# 06_Input_Output.net
KiCad netlist of a schematic drawn in Altium Designer
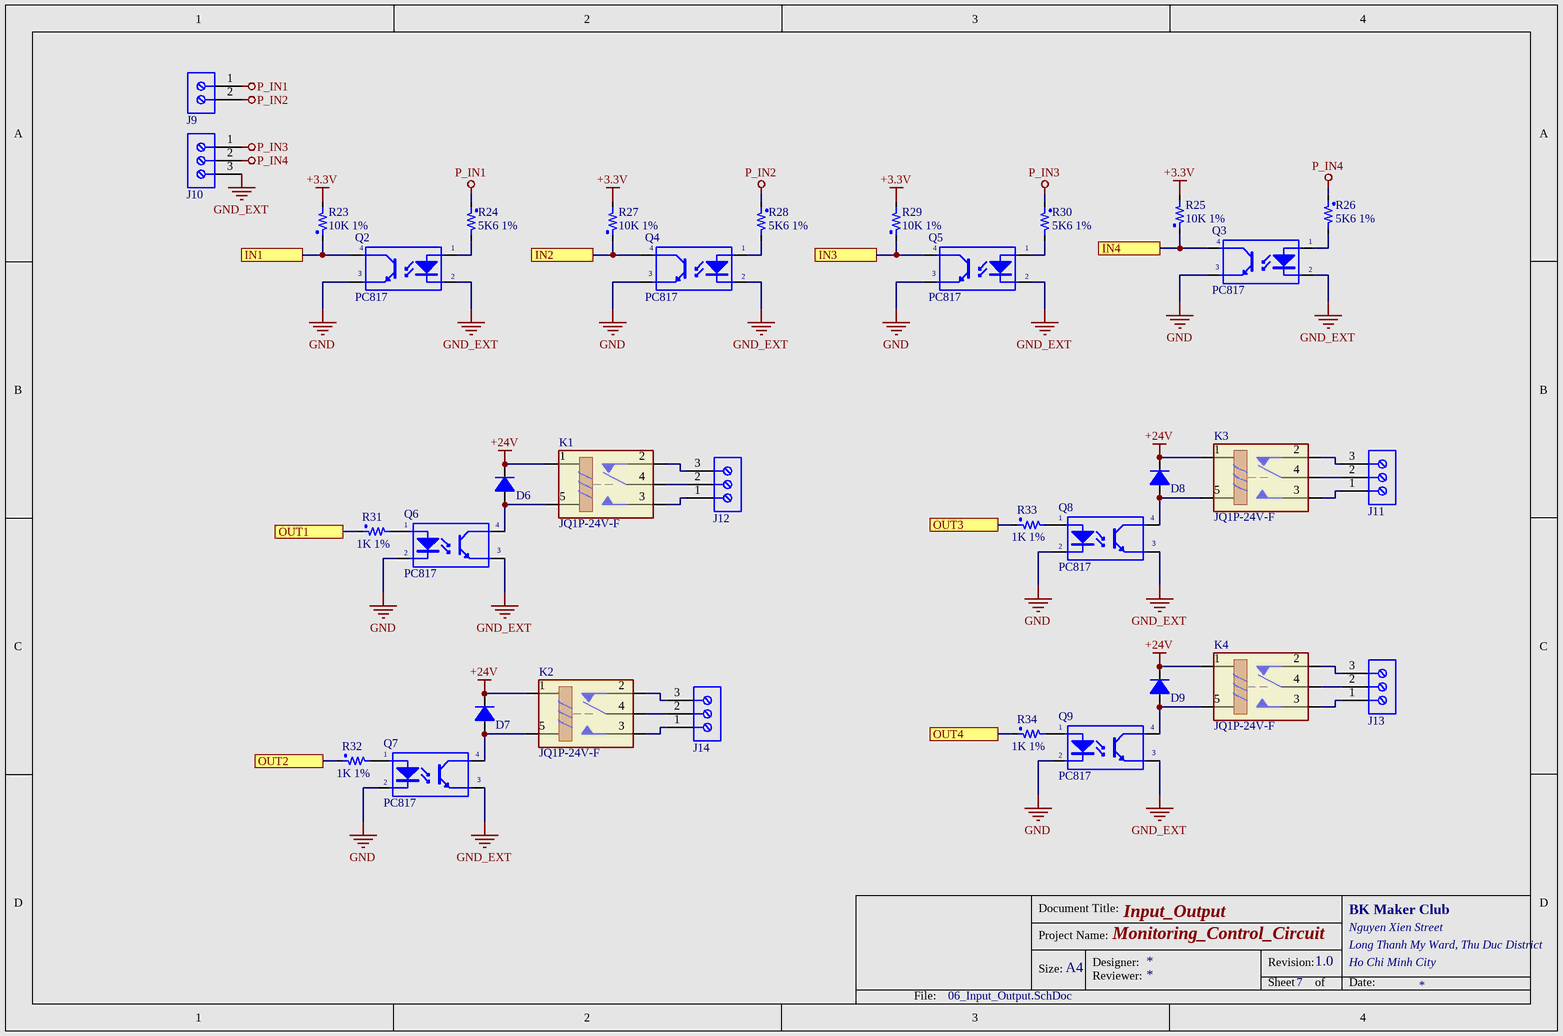
[diagram p0: 06_Input_Output.SchDoc]

(export (version "E")
  (design (tool "Eeschema 10.0.6"))
  (components
    (comp (ref "D6")
      (value "S1M")
      (footprint "Diode:DO-214AC")
      (description "Rectifiers 1.0A 1000V")
      (fields (field (name "MFR") "ON Semiconductor / Fairchild"))
      (libsource (lib "Diode") (part "S1M"))
    )
    (comp (ref "D7")
      (value "S1M")
      (footprint "Diode:DO-214AC")
      (description "Rectifiers 1.0A 1000V")
      (fields (field (name "MFR") "ON Semiconductor / Fairchild"))
      (libsource (lib "Diode") (part "S1M"))
    )
    (comp (ref "D8")
      (value "S1M")
      (footprint "Diode:DO-214AC")
      (description "Rectifiers 1.0A 1000V")
      (fields (field (name "MFR") "ON Semiconductor / Fairchild"))
      (libsource (lib "Diode") (part "S1M"))
    )
    (comp (ref "D9")
      (value "S1M")
      (footprint "Diode:DO-214AC")
      (description "Rectifiers 1.0A 1000V")
      (fields (field (name "MFR") "ON Semiconductor / Fairchild"))
      (libsource (lib "Diode") (part "S1M"))
    )
    (comp (ref "J9")
      (value "691103110002")
      (footprint "691103110002")
      (description "WR-TBL Series 1031 Horizontal Entry Modular, THT, pitch 3.5mm, 2p")
      (fields (field (name "MFR") "Wurth Elektronik"))
      (libsource (lib "Altium_WR-TBL (rev22b)") (part "691103110002"))
    )
    (comp (ref "J10")
      (value "691103110003")
      (footprint "691103110003")
      (description "WR-TBL Series 1031 Horizontal Entry Modular, THT, pitch 3.5mm, 3p")
      (fields (field (name "MFR") "Wurth Elektronik"))
      (libsource (lib "Altium_WR-TBL (rev22b)") (part "691103110003"))
    )
    (comp (ref "J11")
      (value "691103110003")
      (footprint "691103110003")
      (description "WR-TBL Series 1031 Horizontal Entry Modular, THT, pitch 3.5mm, 3p")
      (fields (field (name "MFR") "Wurth Elektronik"))
      (libsource (lib "Altium_WR-TBL (rev22b)") (part "691103110003"))
    )
    (comp (ref "J12")
      (value "691103110003")
      (footprint "691103110003")
      (description "WR-TBL Series 1031 Horizontal Entry Modular, THT, pitch 3.5mm, 3p")
      (fields (field (name "MFR") "Wurth Elektronik"))
      (libsource (lib "Altium_WR-TBL (rev22b)") (part "691103110003"))
    )
    (comp (ref "J13")
      (value "691103110003")
      (footprint "691103110003")
      (description "WR-TBL Series 1031 Horizontal Entry Modular, THT, pitch 3.5mm, 3p")
      (fields (field (name "MFR") "Wurth Elektronik"))
      (libsource (lib "Altium_WR-TBL (rev22b)") (part "691103110003"))
    )
    (comp (ref "J14")
      (value "691103110003")
      (footprint "691103110003")
      (description "WR-TBL Series 1031 Horizontal Entry Modular, THT, pitch 3.5mm, 3p")
      (fields (field (name "MFR") "Wurth Elektronik"))
      (libsource (lib "Altium_WR-TBL (rev22b)") (part "691103110003"))
    )
    (comp (ref "K1")
      (value "JQ1P-24V-F")
      (footprint "JQ1P24VF")
      (description "Relay or Contactor")
      (fields (field (name "MFR") "Panasonic"))
      (libsource (lib "Controller") (part "JQ1P-24V-F"))
    )
    (comp (ref "K2")
      (value "JQ1P-24V-F")
      (footprint "JQ1P24VF")
      (description "Relay or Contactor")
      (fields (field (name "MFR") "Panasonic"))
      (libsource (lib "Controller") (part "JQ1P-24V-F"))
    )
    (comp (ref "K3")
      (value "JQ1P-24V-F")
      (footprint "JQ1P24VF")
      (description "Relay or Contactor")
      (fields (field (name "MFR") "Panasonic"))
      (libsource (lib "Controller") (part "JQ1P-24V-F"))
    )
    (comp (ref "K4")
      (value "JQ1P-24V-F")
      (footprint "JQ1P24VF")
      (description "Relay or Contactor")
      (fields (field (name "MFR") "Panasonic"))
      (libsource (lib "Controller") (part "JQ1P-24V-F"))
    )
    (comp (ref "Q2")
      (value "PC817")
      (footprint "SOP-4")
      (description "Transistor Output Optocouplers Photocoupler")
      (fields (field (name "MFR") "Sharp Microelectronics") (field (name "MFR PART NUMBER") "PC817XNNIP1B"))
      (libsource (lib "Optocoupler") (part "PC817XNNIP1B"))
    )
    (comp (ref "Q3")
      (value "PC817")
      (footprint "SOP-4")
      (description "Transistor Output Optocouplers Photocoupler")
      (fields (field (name "MFR") "Sharp Microelectronics") (field (name "MFR PART NUMBER") "PC817XNNIP1B"))
      (libsource (lib "Optocoupler") (part "PC817XNNIP1B"))
    )
    (comp (ref "Q4")
      (value "PC817")
      (footprint "SOP-4")
      (description "Transistor Output Optocouplers Photocoupler")
      (fields (field (name "MFR") "Sharp Microelectronics") (field (name "MFR PART NUMBER") "PC817XNNIP1B"))
      (libsource (lib "Optocoupler") (part "PC817XNNIP1B"))
    )
    (comp (ref "Q5")
      (value "PC817")
      (footprint "SOP-4")
      (description "Transistor Output Optocouplers Photocoupler")
      (fields (field (name "MFR") "Sharp Microelectronics") (field (name "MFR PART NUMBER") "PC817XNNIP1B"))
      (libsource (lib "Optocoupler") (part "PC817XNNIP1B"))
    )
    (comp (ref "Q6")
      (value "PC817")
      (footprint "SOP-4")
      (description "Transistor Output Optocouplers Photocoupler")
      (fields (field (name "MFR") "Sharp Microelectronics") (field (name "MFR PART NUMBER") "PC817XNNIP1B"))
      (libsource (lib "Optocoupler") (part "PC817XNNIP1B"))
    )
    (comp (ref "Q7")
      (value "PC817")
      (footprint "SOP-4")
      (description "Transistor Output Optocouplers Photocoupler")
      (fields (field (name "MFR") "Sharp Microelectronics") (field (name "MFR PART NUMBER") "PC817XNNIP1B"))
      (libsource (lib "Optocoupler") (part "PC817XNNIP1B"))
    )
    (comp (ref "Q8")
      (value "PC817")
      (footprint "SOP-4")
      (description "Transistor Output Optocouplers Photocoupler")
      (fields (field (name "MFR") "Sharp Microelectronics") (field (name "MFR PART NUMBER") "PC817XNNIP1B"))
      (libsource (lib "Optocoupler") (part "PC817XNNIP1B"))
    )
    (comp (ref "Q9")
      (value "PC817")
      (footprint "SOP-4")
      (description "Transistor Output Optocouplers Photocoupler")
      (fields (field (name "MFR") "Sharp Microelectronics") (field (name "MFR PART NUMBER") "PC817XNNIP1B"))
      (libsource (lib "Optocoupler") (part "PC817XNNIP1B"))
    )
    (comp (ref "R23")
      (value "10K 1%")
      (footprint "Resistor:R0603 (1608 Metric)")
      (description "Thick Film Resistors - SMD 10K OHM 1% Case 0603")
      (fields (field (name "MFR PART NUMBER") "RC0603FR-0710KL") (field (name "MFR") "Yageo"))
      (libsource (lib "ChipResistor") (part "RC0603FR-0710KL"))
    )
    (comp (ref "R24")
      (value "5K6 1%")
      (footprint "Resistor:R0603 (1608 Metric)")
      (description "Thick Film Resistors - SMD 5K6 OHM 1% Case 0603")
      (fields (field (name "MFR PART NUMBER") "RC0603FR-075K6L") (field (name "MFR") "Yageo"))
      (libsource (lib "ChipResistor") (part "RC0603FR-075K6L"))
    )
    (comp (ref "R25")
      (value "10K 1%")
      (footprint "Resistor:R0603 (1608 Metric)")
      (description "Thick Film Resistors - SMD 10K OHM 1% Case 0603")
      (fields (field (name "MFR PART NUMBER") "RC0603FR-0710KL") (field (name "MFR") "Yageo"))
      (libsource (lib "ChipResistor") (part "RC0603FR-0710KL"))
    )
    (comp (ref "R26")
      (value "5K6 1%")
      (footprint "Resistor:R0603 (1608 Metric)")
      (description "Thick Film Resistors - SMD 5K6 OHM 1% Case 0603")
      (fields (field (name "MFR PART NUMBER") "RC0603FR-075K6L") (field (name "MFR") "Yageo"))
      (libsource (lib "ChipResistor") (part "RC0603FR-075K6L"))
    )
    (comp (ref "R27")
      (value "10K 1%")
      (footprint "Resistor:R0603 (1608 Metric)")
      (description "Thick Film Resistors - SMD 10K OHM 1% Case 0603")
      (fields (field (name "MFR PART NUMBER") "RC0603FR-0710KL") (field (name "MFR") "Yageo"))
      (libsource (lib "ChipResistor") (part "RC0603FR-0710KL"))
    )
    (comp (ref "R28")
      (value "5K6 1%")
      (footprint "Resistor:R0603 (1608 Metric)")
      (description "Thick Film Resistors - SMD 5K6 OHM 1% Case 0603")
      (fields (field (name "MFR PART NUMBER") "RC0603FR-075K6L") (field (name "MFR") "Yageo"))
      (libsource (lib "ChipResistor") (part "RC0603FR-075K6L"))
    )
    (comp (ref "R29")
      (value "10K 1%")
      (footprint "Resistor:R0603 (1608 Metric)")
      (description "Thick Film Resistors - SMD 10K OHM 1% Case 0603")
      (fields (field (name "MFR PART NUMBER") "RC0603FR-0710KL") (field (name "MFR") "Yageo"))
      (libsource (lib "ChipResistor") (part "RC0603FR-0710KL"))
    )
    (comp (ref "R30")
      (value "5K6 1%")
      (footprint "Resistor:R0603 (1608 Metric)")
      (description "Thick Film Resistors - SMD 5K6 OHM 1% Case 0603")
      (fields (field (name "MFR PART NUMBER") "RC0603FR-075K6L") (field (name "MFR") "Yageo"))
      (libsource (lib "ChipResistor") (part "RC0603FR-075K6L"))
    )
    (comp (ref "R31")
      (value "1K 1%")
      (footprint "Resistor:R0603 (1608 Metric)")
      (description "Thick Film Resistors - SMD 1K OHM 1% Case 0603")
      (fields (field (name "MFR PART NUMBER") "RC0603FR-071KL") (field (name "MFR") "Yageo"))
      (libsource (lib "ChipResistor") (part "RC0603FR-071KL"))
    )
    (comp (ref "R32")
      (value "1K 1%")
      (footprint "Resistor:R0603 (1608 Metric)")
      (description "Thick Film Resistors - SMD 1K OHM 1% Case 0603")
      (fields (field (name "MFR PART NUMBER") "RC0603FR-071KL") (field (name "MFR") "Yageo"))
      (libsource (lib "ChipResistor") (part "RC0603FR-071KL"))
    )
    (comp (ref "R33")
      (value "1K 1%")
      (footprint "Resistor:R0603 (1608 Metric)")
      (description "Thick Film Resistors - SMD 1K OHM 1% Case 0603")
      (fields (field (name "MFR PART NUMBER") "RC0603FR-071KL") (field (name "MFR") "Yageo"))
      (libsource (lib "ChipResistor") (part "RC0603FR-071KL"))
    )
    (comp (ref "R34")
      (value "1K 1%")
      (footprint "Resistor:R0603 (1608 Metric)")
      (description "Thick Film Resistors - SMD 1K OHM 1% Case 0603")
      (fields (field (name "MFR PART NUMBER") "RC0603FR-071KL") (field (name "MFR") "Yageo"))
      (libsource (lib "ChipResistor") (part "RC0603FR-071KL"))
    )
  )
  (nets
    (net (code "1") (name "+3.3V") (class "Default")
      (node (ref "R23") (pin "2") (pinfunction "2_2") (pintype "passive"))
      (node (ref "R25") (pin "2") (pinfunction "2_2") (pintype "passive"))
      (node (ref "R27") (pin "2") (pinfunction "2_2") (pintype "passive"))
      (node (ref "R29") (pin "2") (pinfunction "2_2") (pintype "passive"))
    )
    (net (code "2") (name "+24V") (class "Default")
      (node (ref "D6") (pin "2") (pinfunction "K_2") (pintype "passive"))
      (node (ref "D7") (pin "2") (pinfunction "K_2") (pintype "passive"))
      (node (ref "D8") (pin "2") (pinfunction "K_2") (pintype "passive"))
      (node (ref "D9") (pin "2") (pinfunction "K_2") (pintype "passive"))
      (node (ref "K1") (pin "1") (pinfunction "COIL1_1") (pintype "passive"))
      (node (ref "K2") (pin "1") (pinfunction "COIL1_1") (pintype "passive"))
      (node (ref "K3") (pin "1") (pinfunction "COIL1_1") (pintype "passive"))
      (node (ref "K4") (pin "1") (pinfunction "COIL1_1") (pintype "passive"))
    )
    (net (code "3") (name "/IN1") (class "Default")
      (node (ref "Q2") (pin "4") (pinfunction "C_4") (pintype "passive"))
      (node (ref "R23") (pin "1") (pinfunction "1_1") (pintype "passive"))
    )
    (net (code "4") (name "/IN2") (class "Default")
      (node (ref "Q4") (pin "4") (pinfunction "C_4") (pintype "passive"))
      (node (ref "R27") (pin "1") (pinfunction "1_1") (pintype "passive"))
    )
    (net (code "5") (name "/IN3") (class "Default")
      (node (ref "Q5") (pin "4") (pinfunction "C_4") (pintype "passive"))
      (node (ref "R29") (pin "1") (pinfunction "1_1") (pintype "passive"))
    )
    (net (code "6") (name "/IN4") (class "Default")
      (node (ref "Q3") (pin "4") (pinfunction "C_4") (pintype "passive"))
      (node (ref "R25") (pin "1") (pinfunction "1_1") (pintype "passive"))
    )
    (net (code "7") (name "/OUT1") (class "Default")
      (node (ref "R31") (pin "1") (pinfunction "1_1") (pintype "passive"))
    )
    (net (code "8") (name "/OUT2") (class "Default")
      (node (ref "R32") (pin "1") (pinfunction "1_1") (pintype "passive"))
    )
    (net (code "9") (name "/OUT3") (class "Default")
      (node (ref "R33") (pin "1") (pinfunction "1_1") (pintype "passive"))
    )
    (net (code "10") (name "/OUT4") (class "Default")
      (node (ref "R34") (pin "1") (pinfunction "1_1") (pintype "passive"))
    )
    (net (code "11") (name "GND") (class "Default")
      (node (ref "Q2") (pin "3") (pinfunction "E_3") (pintype "passive"))
      (node (ref "Q3") (pin "3") (pinfunction "E_3") (pintype "passive"))
      (node (ref "Q4") (pin "3") (pinfunction "E_3") (pintype "passive"))
      (node (ref "Q5") (pin "3") (pinfunction "E_3") (pintype "passive"))
      (node (ref "Q6") (pin "2") (pinfunction "K_2") (pintype "passive"))
      (node (ref "Q7") (pin "2") (pinfunction "K_2") (pintype "passive"))
      (node (ref "Q8") (pin "2") (pinfunction "K_2") (pintype "passive"))
      (node (ref "Q9") (pin "2") (pinfunction "K_2") (pintype "passive"))
    )
    (net (code "12") (name "GND_EXT") (class "Default")
      (node (ref "J10") (pin "3") (pinfunction "3_3") (pintype "passive"))
      (node (ref "Q2") (pin "2") (pinfunction "K_2") (pintype "passive"))
      (node (ref "Q3") (pin "2") (pinfunction "K_2") (pintype "passive"))
      (node (ref "Q4") (pin "2") (pinfunction "K_2") (pintype "passive"))
      (node (ref "Q5") (pin "2") (pinfunction "K_2") (pintype "passive"))
      (node (ref "Q6") (pin "3") (pinfunction "E_3") (pintype "passive"))
      (node (ref "Q7") (pin "3") (pinfunction "E_3") (pintype "passive"))
      (node (ref "Q8") (pin "3") (pinfunction "E_3") (pintype "passive"))
      (node (ref "Q9") (pin "3") (pinfunction "E_3") (pintype "passive"))
    )
    (net (code "13") (name "Net-(D6-A)") (class "Default")
      (node (ref "D6") (pin "1") (pinfunction "A_1") (pintype "passive"))
      (node (ref "K1") (pin "5") (pinfunction "COIL2_5") (pintype "passive"))
      (node (ref "Q6") (pin "4") (pinfunction "C_4") (pintype "passive"))
    )
    (net (code "14") (name "Net-(D7-A)") (class "Default")
      (node (ref "D7") (pin "1") (pinfunction "A_1") (pintype "passive"))
      (node (ref "K2") (pin "5") (pinfunction "COIL2_5") (pintype "passive"))
      (node (ref "Q7") (pin "4") (pinfunction "C_4") (pintype "passive"))
    )
    (net (code "15") (name "Net-(D8-A)") (class "Default")
      (node (ref "D8") (pin "1") (pinfunction "A_1") (pintype "passive"))
      (node (ref "K3") (pin "5") (pinfunction "COIL2_5") (pintype "passive"))
      (node (ref "Q8") (pin "4") (pinfunction "C_4") (pintype "passive"))
    )
    (net (code "16") (name "Net-(D9-A)") (class "Default")
      (node (ref "D9") (pin "1") (pinfunction "A_1") (pintype "passive"))
      (node (ref "K4") (pin "5") (pinfunction "COIL2_5") (pintype "passive"))
      (node (ref "Q9") (pin "4") (pinfunction "C_4") (pintype "passive"))
    )
    (net (code "17") (name "Net-(K1-COM)") (class "Default")
      (node (ref "J12") (pin "2") (pinfunction "2_2") (pintype "passive"))
      (node (ref "K1") (pin "4") (pinfunction "COM_4") (pintype "passive"))
    )
    (net (code "18") (name "Net-(K1-NC)") (class "Default")
      (node (ref "J12") (pin "3") (pinfunction "3_3") (pintype "passive"))
      (node (ref "K1") (pin "2") (pinfunction "NC_2") (pintype "passive"))
    )
    (net (code "19") (name "Net-(K1-NO)") (class "Default")
      (node (ref "J12") (pin "1") (pinfunction "1_1") (pintype "passive"))
      (node (ref "K1") (pin "3") (pinfunction "NO_3") (pintype "passive"))
    )
    (net (code "20") (name "Net-(K2-COM)") (class "Default")
      (node (ref "J14") (pin "2") (pinfunction "2_2") (pintype "passive"))
      (node (ref "K2") (pin "4") (pinfunction "COM_4") (pintype "passive"))
    )
    (net (code "21") (name "Net-(K2-NC)") (class "Default")
      (node (ref "J14") (pin "3") (pinfunction "3_3") (pintype "passive"))
      (node (ref "K2") (pin "2") (pinfunction "NC_2") (pintype "passive"))
    )
    (net (code "22") (name "Net-(K2-NO)") (class "Default")
      (node (ref "J14") (pin "1") (pinfunction "1_1") (pintype "passive"))
      (node (ref "K2") (pin "3") (pinfunction "NO_3") (pintype "passive"))
    )
    (net (code "23") (name "Net-(K3-COM)") (class "Default")
      (node (ref "J11") (pin "2") (pinfunction "2_2") (pintype "passive"))
      (node (ref "K3") (pin "4") (pinfunction "COM_4") (pintype "passive"))
    )
    (net (code "24") (name "Net-(K3-NC)") (class "Default")
      (node (ref "J11") (pin "3") (pinfunction "3_3") (pintype "passive"))
      (node (ref "K3") (pin "2") (pinfunction "NC_2") (pintype "passive"))
    )
    (net (code "25") (name "Net-(K3-NO)") (class "Default")
      (node (ref "J11") (pin "1") (pinfunction "1_1") (pintype "passive"))
      (node (ref "K3") (pin "3") (pinfunction "NO_3") (pintype "passive"))
    )
    (net (code "26") (name "Net-(K4-COM)") (class "Default")
      (node (ref "J13") (pin "2") (pinfunction "2_2") (pintype "passive"))
      (node (ref "K4") (pin "4") (pinfunction "COM_4") (pintype "passive"))
    )
    (net (code "27") (name "Net-(K4-NC)") (class "Default")
      (node (ref "J13") (pin "3") (pinfunction "3_3") (pintype "passive"))
      (node (ref "K4") (pin "2") (pinfunction "NC_2") (pintype "passive"))
    )
    (net (code "28") (name "Net-(K4-NO)") (class "Default")
      (node (ref "J13") (pin "1") (pinfunction "1_1") (pintype "passive"))
      (node (ref "K4") (pin "3") (pinfunction "NO_3") (pintype "passive"))
    )
    (net (code "29") (name "Net-(Q2-A)") (class "Default")
      (node (ref "Q2") (pin "1") (pinfunction "A_1") (pintype "passive"))
      (node (ref "R24") (pin "2") (pinfunction "2_2") (pintype "passive"))
    )
    (net (code "30") (name "Net-(Q3-A)") (class "Default")
      (node (ref "Q3") (pin "1") (pinfunction "A_1") (pintype "passive"))
      (node (ref "R26") (pin "2") (pinfunction "2_2") (pintype "passive"))
    )
    (net (code "31") (name "Net-(Q4-A)") (class "Default")
      (node (ref "Q4") (pin "1") (pinfunction "A_1") (pintype "passive"))
      (node (ref "R28") (pin "2") (pinfunction "2_2") (pintype "passive"))
    )
    (net (code "32") (name "Net-(Q5-A)") (class "Default")
      (node (ref "Q5") (pin "1") (pinfunction "A_1") (pintype "passive"))
      (node (ref "R30") (pin "2") (pinfunction "2_2") (pintype "passive"))
    )
    (net (code "33") (name "Net-(Q6-A)") (class "Default")
      (node (ref "Q6") (pin "1") (pinfunction "A_1") (pintype "passive"))
      (node (ref "R31") (pin "2") (pinfunction "2_2") (pintype "passive"))
    )
    (net (code "34") (name "Net-(Q7-A)") (class "Default")
      (node (ref "Q7") (pin "1") (pinfunction "A_1") (pintype "passive"))
      (node (ref "R32") (pin "2") (pinfunction "2_2") (pintype "passive"))
    )
    (net (code "35") (name "Net-(Q8-A)") (class "Default")
      (node (ref "Q8") (pin "1") (pinfunction "A_1") (pintype "passive"))
      (node (ref "R33") (pin "2") (pinfunction "2_2") (pintype "passive"))
    )
    (net (code "36") (name "Net-(Q9-A)") (class "Default")
      (node (ref "Q9") (pin "1") (pinfunction "A_1") (pintype "passive"))
      (node (ref "R34") (pin "2") (pinfunction "2_2") (pintype "passive"))
    )
    (net (code "37") (name "P_IN1") (class "Default")
      (node (ref "J9") (pin "1") (pinfunction "1_1") (pintype "passive"))
      (node (ref "R24") (pin "1") (pinfunction "1_1") (pintype "passive"))
    )
    (net (code "38") (name "P_IN2") (class "Default")
      (node (ref "J9") (pin "2") (pinfunction "2_2") (pintype "passive"))
      (node (ref "R28") (pin "1") (pinfunction "1_1") (pintype "passive"))
    )
    (net (code "39") (name "P_IN3") (class "Default")
      (node (ref "J10") (pin "1") (pinfunction "1_1") (pintype "passive"))
      (node (ref "R30") (pin "1") (pinfunction "1_1") (pintype "passive"))
    )
    (net (code "40") (name "P_IN4") (class "Default")
      (node (ref "J10") (pin "2") (pinfunction "2_2") (pintype "passive"))
      (node (ref "R26") (pin "1") (pinfunction "1_1") (pintype "passive"))
    )
  )
)
